# 18066_0.net
KiCad netlist of a schematic drawn in EAGLE
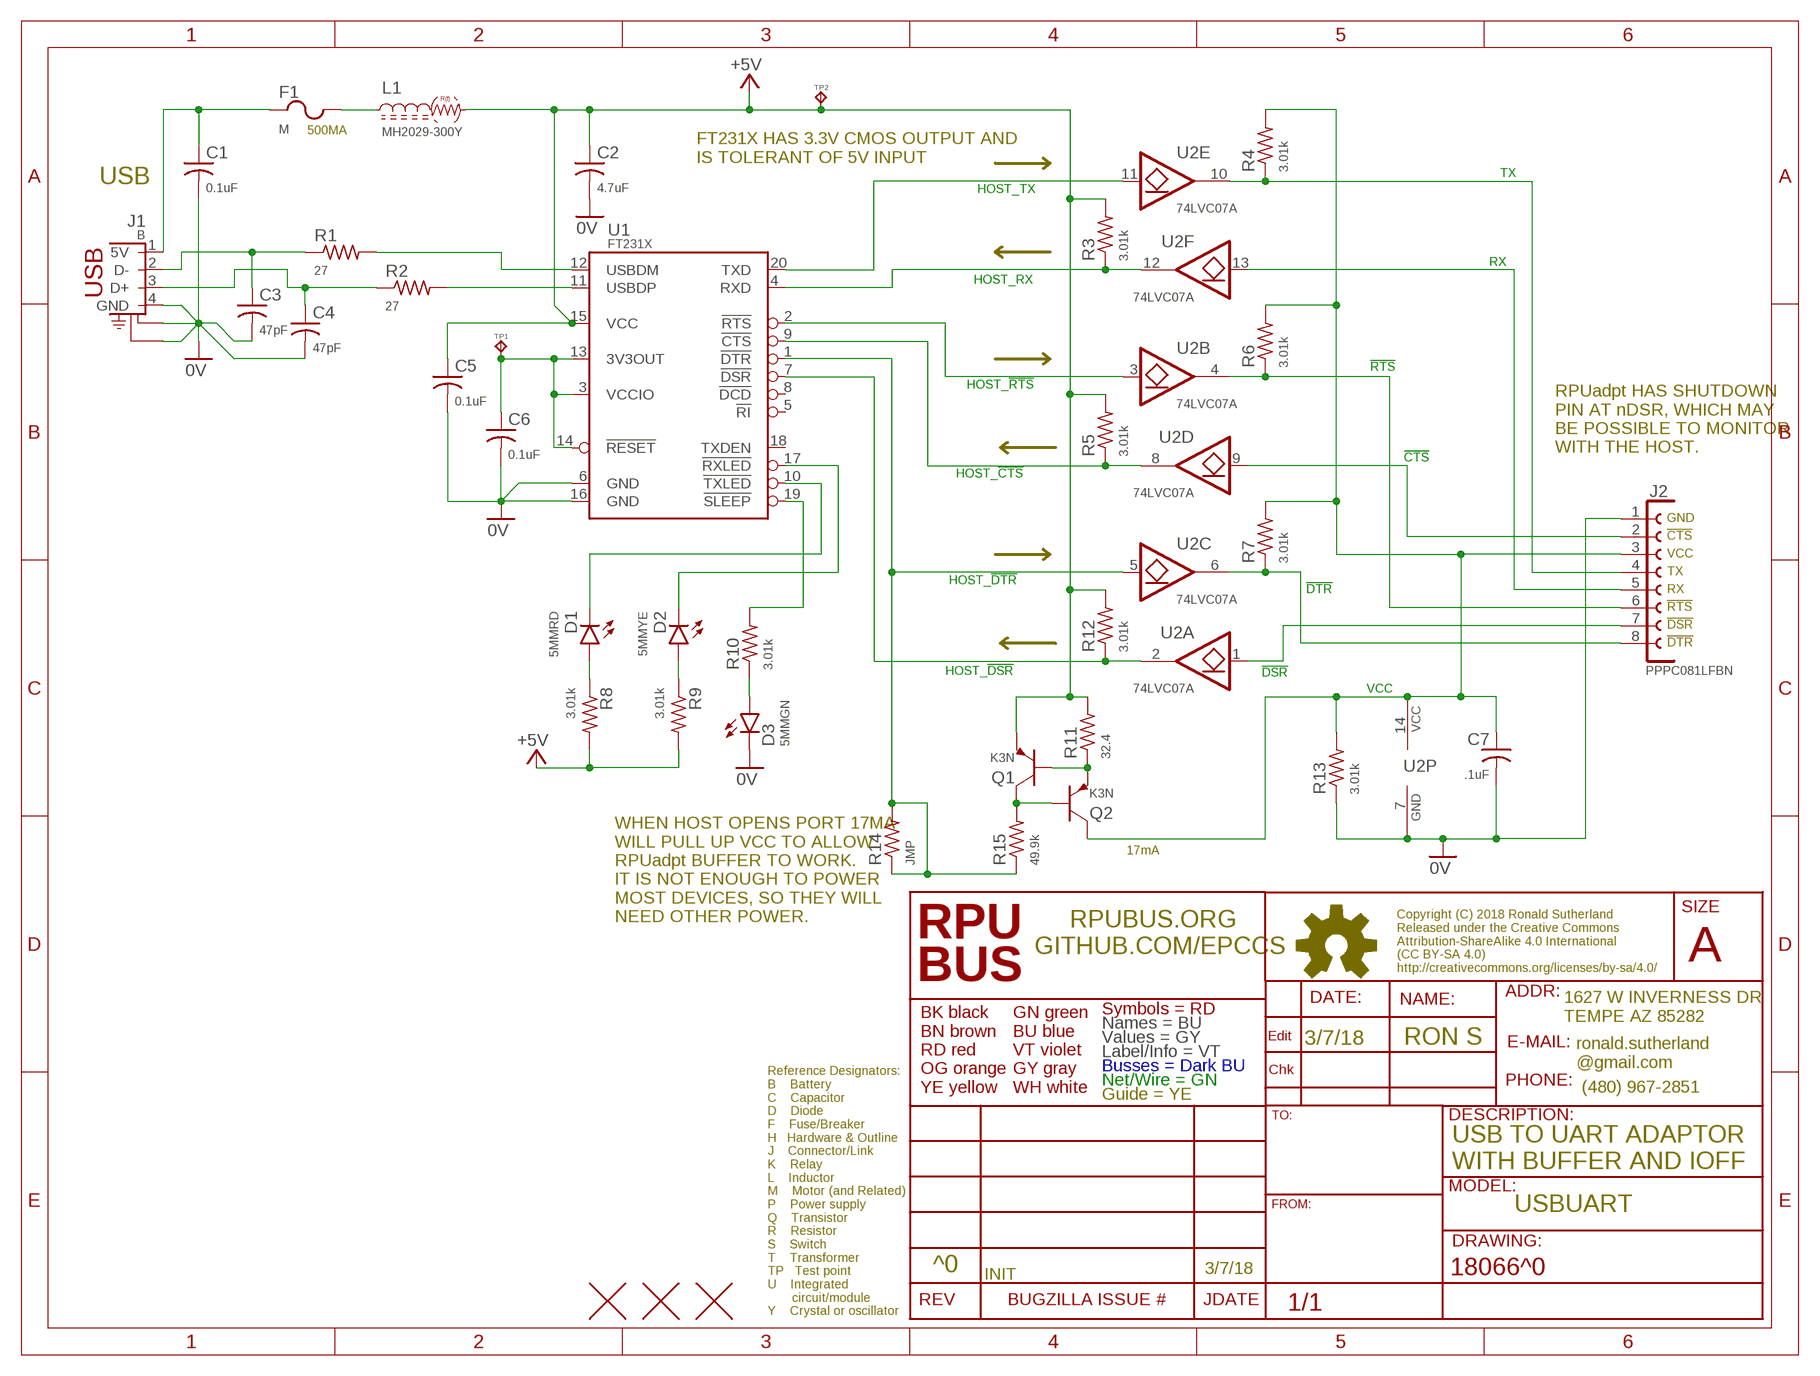
[diagram p0: schematic, sheet 1]

(export (version "E")
  (design (tool "Eeschema 10.0.6"))
  (components
    (comp (ref "C1")
      (value "0.1uF")
      (footprint "eagle-import:C0603(1608)")
      (libsource (lib "eagle-import") (part "CC0603A"))
    )
    (comp (ref "C2")
      (value "4.7uF")
      (footprint "eagle-import:C1206(3216)")
      (libsource (lib "eagle-import") (part "CC1206"))
    )
    (comp (ref "C3")
      (value "47pF")
      (footprint "eagle-import:C0603(1608)")
      (libsource (lib "eagle-import") (part "CC0603A"))
    )
    (comp (ref "C4")
      (value "47pF")
      (footprint "eagle-import:C0603(1608)")
      (libsource (lib "eagle-import") (part "CC0603A"))
    )
    (comp (ref "C5")
      (value "0.1uF")
      (footprint "eagle-import:C0603(1608)")
      (libsource (lib "eagle-import") (part "CC0603A"))
    )
    (comp (ref "C6")
      (value "0.1uF")
      (footprint "eagle-import:C0603(1608)")
      (libsource (lib "eagle-import") (part "CC0603A"))
    )
    (comp (ref "C7")
      (value ".1uF")
      (footprint "eagle-import:C0603(1608)")
      (libsource (lib "eagle-import") (part "CC0603A"))
    )
    (comp (ref "D1")
      (value "5MMRD")
      (footprint "eagle-import:LED5MM")
      (libsource (lib "eagle-import") (part "LED5MM"))
    )
    (comp (ref "D2")
      (value "5MMYE")
      (footprint "eagle-import:LED5MM")
      (libsource (lib "eagle-import") (part "LED5MM"))
    )
    (comp (ref "D3")
      (value "5MMGN")
      (footprint "eagle-import:LED5MM")
      (libsource (lib "eagle-import") (part "LED5MM"))
    )
    (comp (ref "F1")
      (value "M")
      (footprint "eagle-import:C1210(3225)")
      (libsource (lib "eagle-import") (part "SMD1210"))
    )
    (comp (ref "J1")
      (value "B")
      (footprint "eagle-import:USB-B-PTH")
      (libsource (lib "eagle-import") (part "B"))
    )
    (comp (ref "J2")
      (value "PPPC081LFBN")
      (footprint "eagle-import:F1X8")
      (libsource (lib "eagle-import") (part "F1X8"))
    )
    (comp (ref "L1")
      (value "MH2029-300Y")
      (footprint "eagle-import:C0805(2012)")
      (libsource (lib "eagle-import") (part "L0805"))
    )
    (comp (ref "Q1")
      (value "K3N")
      (footprint "eagle-import:SOT23")
      (libsource (lib "eagle-import") (part "PNPSOT23"))
    )
    (comp (ref "Q2")
      (value "K3N")
      (footprint "eagle-import:SOT23")
      (libsource (lib "eagle-import") (part "PNPSOT23"))
    )
    (comp (ref "R1")
      (value "27")
      (footprint "eagle-import:C0805(2012)")
      (libsource (lib "eagle-import") (part "R0805"))
    )
    (comp (ref "R2")
      (value "27")
      (footprint "eagle-import:C0805(2012)")
      (libsource (lib "eagle-import") (part "R0805"))
    )
    (comp (ref "R3")
      (value "3.01k")
      (footprint "eagle-import:C0805(2012)")
      (libsource (lib "eagle-import") (part "R0805"))
    )
    (comp (ref "R4")
      (value "3.01k")
      (footprint "eagle-import:C0805(2012)")
      (libsource (lib "eagle-import") (part "R0805"))
    )
    (comp (ref "R5")
      (value "3.01k")
      (footprint "eagle-import:C0805(2012)")
      (libsource (lib "eagle-import") (part "R0805"))
    )
    (comp (ref "R6")
      (value "3.01k")
      (footprint "eagle-import:C0805(2012)")
      (libsource (lib "eagle-import") (part "R0805"))
    )
    (comp (ref "R7")
      (value "3.01k")
      (footprint "eagle-import:C0805(2012)")
      (libsource (lib "eagle-import") (part "R0805"))
    )
    (comp (ref "R8")
      (value "3.01k")
      (footprint "eagle-import:C0805(2012)")
      (libsource (lib "eagle-import") (part "R0805"))
    )
    (comp (ref "R9")
      (value "3.01k")
      (footprint "eagle-import:C0805(2012)")
      (libsource (lib "eagle-import") (part "R0805"))
    )
    (comp (ref "R10")
      (value "3.01k")
      (footprint "eagle-import:C0805(2012)")
      (libsource (lib "eagle-import") (part "R0805"))
    )
    (comp (ref "R11")
      (value "32.4")
      (footprint "eagle-import:C0805(2012)")
      (libsource (lib "eagle-import") (part "R0805"))
    )
    (comp (ref "R12")
      (value "3.01k")
      (footprint "eagle-import:C0805(2012)")
      (libsource (lib "eagle-import") (part "R0805"))
    )
    (comp (ref "R13")
      (value "3.01k")
      (footprint "eagle-import:C0805(2012)")
      (libsource (lib "eagle-import") (part "R0805"))
    )
    (comp (ref "R14")
      (value "JMP")
      (footprint "eagle-import:C0805(2012)")
      (libsource (lib "eagle-import") (part "R0805"))
    )
    (comp (ref "R15")
      (value "49.9k")
      (footprint "eagle-import:C0805(2012)")
      (libsource (lib "eagle-import") (part "R0805"))
    )
    (comp (ref "TP1")
      (value "TPPAD1-08")
      (footprint "eagle-import:P1-08")
      (libsource (lib "eagle-import") (part "TPPAD1-08"))
    )
    (comp (ref "TP2")
      (value "TPPAD1-08")
      (footprint "eagle-import:P1-08")
      (libsource (lib "eagle-import") (part "TPPAD1-08"))
    )
    (comp (ref "U$2")
      (value "FIDUCIAL1.27")
      (footprint "eagle-import:FIDUCIAL-1.27")
      (libsource (lib "eagle-import") (part "FIDUCIAL1.27"))
    )
    (comp (ref "U$3")
      (value "FIDUCIAL1.27")
      (footprint "eagle-import:FIDUCIAL-1.27")
      (libsource (lib "eagle-import") (part "FIDUCIAL1.27"))
    )
    (comp (ref "U$4")
      (value "FIDUCIAL1.27")
      (footprint "eagle-import:FIDUCIAL-1.27")
      (libsource (lib "eagle-import") (part "FIDUCIAL1.27"))
    )
    (comp (ref "U1")
      (value "FT231X")
      (footprint "eagle-import:20SSOP")
      (libsource (lib "eagle-import") (part "FT231X"))
    )
    (comp (ref "U2")
      (value "74LVC07A")
      (footprint "eagle-import:14SOIC")
      (libsource (lib "eagle-import") (part "7407D"))
    )
  )
  (nets
    (net (code "1") (name "+5V") (class "Default")
      (node (ref "C2") (pin "1") (pinfunction "1_1") (pintype "passive"))
      (node (ref "C5") (pin "1") (pinfunction "1_1") (pintype "passive"))
      (node (ref "L1") (pin "2") (pinfunction "2_2") (pintype "passive"))
      (node (ref "Q1") (pin "E") (pinfunction "E_E") (pintype "passive"))
      (node (ref "R11") (pin "2") (pinfunction "2_2") (pintype "passive"))
      (node (ref "R12") (pin "2") (pinfunction "2_2") (pintype "passive"))
      (node (ref "R3") (pin "2") (pinfunction "2_2") (pintype "passive"))
      (node (ref "R5") (pin "2") (pinfunction "2_2") (pintype "passive"))
      (node (ref "R8") (pin "2") (pinfunction "2_2") (pintype "passive"))
      (node (ref "R9") (pin "2") (pinfunction "2_2") (pintype "passive"))
      (node (ref "TP2") (pin "TP") (pinfunction "TP_TP") (pintype "input"))
      (node (ref "U1") (pin "15") (pinfunction "VCC_15") (pintype "power_in"))
    )
    (net (code "2") (name "/HOST_RX") (class "Default")
      (node (ref "R3") (pin "1") (pinfunction "1_1") (pintype "passive"))
      (node (ref "U1") (pin "4") (pinfunction "RXD_4") (pintype "input"))
      (node (ref "U2") (pin "12") (pinfunction "O_12") (pintype "open_collector"))
    )
    (net (code "3") (name "/HOST_TX") (class "Default")
      (node (ref "U1") (pin "20") (pinfunction "TXD_20") (pintype "output"))
      (node (ref "U2") (pin "11") (pinfunction "I_11") (pintype "input"))
    )
    (net (code "4") (name "/HOST_~{CTS}") (class "Default")
      (node (ref "R5") (pin "1") (pinfunction "1_1") (pintype "passive"))
      (node (ref "U1") (pin "9") (pinfunction "~{CTS}_9") (pintype "input"))
      (node (ref "U2") (pin "8") (pinfunction "O_8") (pintype "open_collector"))
    )
    (net (code "5") (name "/HOST_~{DSR}") (class "Default")
      (node (ref "R12") (pin "1") (pinfunction "1_1") (pintype "passive"))
      (node (ref "U1") (pin "7") (pinfunction "~{DSR}_7") (pintype "input"))
      (node (ref "U2") (pin "2") (pinfunction "O_2") (pintype "open_collector"))
    )
    (net (code "6") (name "/HOST_~{DTR}") (class "Default")
      (node (ref "R14") (pin "1") (pinfunction "1_1") (pintype "passive"))
      (node (ref "R14") (pin "2") (pinfunction "2_2") (pintype "passive"))
      (node (ref "R15") (pin "1") (pinfunction "1_1") (pintype "passive"))
      (node (ref "U1") (pin "1") (pinfunction "~{DTR}_1") (pintype "output"))
      (node (ref "U2") (pin "5") (pinfunction "I_5") (pintype "input"))
    )
    (net (code "7") (name "/HOST_~{RTS}") (class "Default")
      (node (ref "U1") (pin "2") (pinfunction "~{RTS}_2") (pintype "output"))
      (node (ref "U2") (pin "3") (pinfunction "I_3") (pintype "input"))
    )
    (net (code "8") (name "/RX") (class "Default")
      (node (ref "J2") (pin "5") (pinfunction "5_5") (pintype "passive"))
      (node (ref "U2") (pin "13") (pinfunction "I_13") (pintype "input"))
    )
    (net (code "9") (name "/TX") (class "Default")
      (node (ref "J2") (pin "4") (pinfunction "4_4") (pintype "passive"))
      (node (ref "R4") (pin "1") (pinfunction "1_1") (pintype "passive"))
      (node (ref "U2") (pin "10") (pinfunction "O_10") (pintype "open_collector"))
    )
    (net (code "10") (name "/VCC") (class "Default")
      (node (ref "C7") (pin "1") (pinfunction "1_1") (pintype "passive"))
      (node (ref "J2") (pin "3") (pinfunction "3_3") (pintype "passive"))
      (node (ref "Q2") (pin "C") (pinfunction "C_C") (pintype "passive"))
      (node (ref "R13") (pin "2") (pinfunction "2_2") (pintype "passive"))
      (node (ref "R4") (pin "2") (pinfunction "2_2") (pintype "passive"))
      (node (ref "R6") (pin "2") (pinfunction "2_2") (pintype "passive"))
      (node (ref "R7") (pin "2") (pinfunction "2_2") (pintype "passive"))
      (node (ref "U2") (pin "14") (pinfunction "VCC_14") (pintype "power_in"))
    )
    (net (code "11") (name "/~{CTS}") (class "Default")
      (node (ref "J2") (pin "2") (pinfunction "2_2") (pintype "passive"))
      (node (ref "U2") (pin "9") (pinfunction "I_9") (pintype "input"))
    )
    (net (code "12") (name "/~{DSR}") (class "Default")
      (node (ref "J2") (pin "7") (pinfunction "7_7") (pintype "passive"))
      (node (ref "U2") (pin "1") (pinfunction "I_1") (pintype "input"))
    )
    (net (code "13") (name "/~{DTR}") (class "Default")
      (node (ref "J2") (pin "8") (pinfunction "8_8") (pintype "passive"))
      (node (ref "R7") (pin "1") (pinfunction "1_1") (pintype "passive"))
      (node (ref "U2") (pin "6") (pinfunction "O_6") (pintype "open_collector"))
    )
    (net (code "14") (name "/~{RTS}") (class "Default")
      (node (ref "J2") (pin "6") (pinfunction "6_6") (pintype "passive"))
      (node (ref "R6") (pin "1") (pinfunction "1_1") (pintype "passive"))
      (node (ref "U2") (pin "4") (pinfunction "O_4") (pintype "open_collector"))
    )
    (net (code "15") (name "0V") (class "Default")
      (node (ref "C1") (pin "2") (pinfunction "2_2") (pintype "passive"))
      (node (ref "C2") (pin "2") (pinfunction "2_2") (pintype "passive"))
      (node (ref "C3") (pin "2") (pinfunction "2_2") (pintype "passive"))
      (node (ref "C4") (pin "2") (pinfunction "2_2") (pintype "passive"))
      (node (ref "C5") (pin "2") (pinfunction "2_2") (pintype "passive"))
      (node (ref "C6") (pin "2") (pinfunction "2_2") (pintype "passive"))
      (node (ref "C7") (pin "2") (pinfunction "2_2") (pintype "passive"))
      (node (ref "D3") (pin "K") (pinfunction "K_K") (pintype "passive"))
      (node (ref "J1") (pin "4") (pinfunction "GND_4") (pintype "bidirectional"))
      (node (ref "J1") (pin "S1") (pinfunction "CHASSIS1_S1") (pintype "bidirectional"))
      (node (ref "J1") (pin "S2") (pinfunction "CHASSIS2_S2") (pintype "bidirectional"))
      (node (ref "J2") (pin "1") (pinfunction "1_1") (pintype "passive"))
      (node (ref "R13") (pin "1") (pinfunction "1_1") (pintype "passive"))
      (node (ref "U1") (pin "16") (pinfunction "GND_16") (pintype "power_in"))
      (node (ref "U1") (pin "6") (pinfunction "GND_6") (pintype "power_in"))
      (node (ref "U2") (pin "7") (pinfunction "GND_7") (pintype "power_in"))
    )
    (net (code "16") (name "Net-(D1-PadA)") (class "Default")
      (node (ref "D1") (pin "A") (pinfunction "A_A") (pintype "passive"))
      (node (ref "R8") (pin "1") (pinfunction "1_1") (pintype "passive"))
    )
    (net (code "17") (name "Net-(D2-PadA)") (class "Default")
      (node (ref "D2") (pin "A") (pinfunction "A_A") (pintype "passive"))
      (node (ref "R9") (pin "1") (pinfunction "1_1") (pintype "passive"))
    )
    (net (code "18") (name "Net-(D3-PadA)") (class "Default")
      (node (ref "D3") (pin "A") (pinfunction "A_A") (pintype "passive"))
      (node (ref "R10") (pin "1") (pinfunction "1_1") (pintype "passive"))
    )
    (net (code "19") (name "Net-(F1-Pad2)") (class "Default")
      (node (ref "F1") (pin "2") (pinfunction "2_2") (pintype "passive"))
      (node (ref "L1") (pin "1") (pinfunction "1_1") (pintype "passive"))
    )
    (net (code "20") (name "Net-(J1-5V)") (class "Default")
      (node (ref "C1") (pin "1") (pinfunction "1_1") (pintype "passive"))
      (node (ref "F1") (pin "1") (pinfunction "1_1") (pintype "passive"))
      (node (ref "J1") (pin "1") (pinfunction "5V_1") (pintype "bidirectional"))
    )
    (net (code "21") (name "Net-(J1-D+)") (class "Default")
      (node (ref "C4") (pin "1") (pinfunction "1_1") (pintype "passive"))
      (node (ref "J1") (pin "3") (pinfunction "D+_3") (pintype "bidirectional"))
      (node (ref "R2") (pin "1") (pinfunction "1_1") (pintype "passive"))
    )
    (net (code "22") (name "Net-(J1-D-)") (class "Default")
      (node (ref "C3") (pin "1") (pinfunction "1_1") (pintype "passive"))
      (node (ref "J1") (pin "2") (pinfunction "D-_2") (pintype "bidirectional"))
      (node (ref "R1") (pin "1") (pinfunction "1_1") (pintype "passive"))
    )
    (net (code "23") (name "Net-(Q1-PadB)") (class "Default")
      (node (ref "Q1") (pin "B") (pinfunction "B_B") (pintype "passive"))
      (node (ref "Q2") (pin "E") (pinfunction "E_E") (pintype "passive"))
      (node (ref "R11") (pin "1") (pinfunction "1_1") (pintype "passive"))
    )
    (net (code "24") (name "Net-(Q1-PadC)") (class "Default")
      (node (ref "Q1") (pin "C") (pinfunction "C_C") (pintype "passive"))
      (node (ref "Q2") (pin "B") (pinfunction "B_B") (pintype "passive"))
      (node (ref "R15") (pin "2") (pinfunction "2_2") (pintype "passive"))
    )
    (net (code "25") (name "Net-(U1-3V3OUT)") (class "Default")
      (node (ref "C6") (pin "1") (pinfunction "1_1") (pintype "passive"))
      (node (ref "TP1") (pin "TP") (pinfunction "TP_TP") (pintype "input"))
      (node (ref "U1") (pin "13") (pinfunction "3V3OUT_13") (pintype "output"))
      (node (ref "U1") (pin "14") (pinfunction "~{RESET}_14") (pintype "input"))
      (node (ref "U1") (pin "3") (pinfunction "VCCIO_3") (pintype "power_in"))
    )
    (net (code "26") (name "Net-(U1-USBDM)") (class "Default")
      (node (ref "R1") (pin "2") (pinfunction "2_2") (pintype "passive"))
      (node (ref "U1") (pin "12") (pinfunction "USBDM_12") (pintype "input"))
    )
    (net (code "27") (name "Net-(U1-USBDP)") (class "Default")
      (node (ref "R2") (pin "2") (pinfunction "2_2") (pintype "passive"))
      (node (ref "U1") (pin "11") (pinfunction "USBDP_11") (pintype "input"))
    )
    (net (code "28") (name "Net-(U1-~{RXLED})") (class "Default")
      (node (ref "D2") (pin "K") (pinfunction "K_K") (pintype "passive"))
      (node (ref "U1") (pin "17") (pinfunction "~{RXLED}_17") (pintype "output"))
    )
    (net (code "29") (name "Net-(U1-~{SLEEP})") (class "Default")
      (node (ref "R10") (pin "2") (pinfunction "2_2") (pintype "passive"))
      (node (ref "U1") (pin "19") (pinfunction "~{SLEEP}_19") (pintype "output"))
    )
    (net (code "30") (name "Net-(U1-~{TXLED})") (class "Default")
      (node (ref "D1") (pin "K") (pinfunction "K_K") (pintype "passive"))
      (node (ref "U1") (pin "10") (pinfunction "~{TXLED}_10") (pintype "output"))
    )
    (net (code "31") (name "unconnected-(U1-TXDEN-Pad18)") (class "Default")
      (node (ref "U1") (pin "18") (pinfunction "TXDEN_18") (pintype "output"))
    )
    (net (code "32") (name "unconnected-(U1-~{DCD}-Pad8)") (class "Default")
      (node (ref "U1") (pin "8") (pinfunction "~{DCD}_8") (pintype "input"))
    )
    (net (code "33") (name "unconnected-(U1-~{RI}-Pad5)") (class "Default")
      (node (ref "U1") (pin "5") (pinfunction "~{RI}_5") (pintype "input"))
    )
  )
)
